# design.net
KiCad netlist of a schematic drawn in Altium Designer
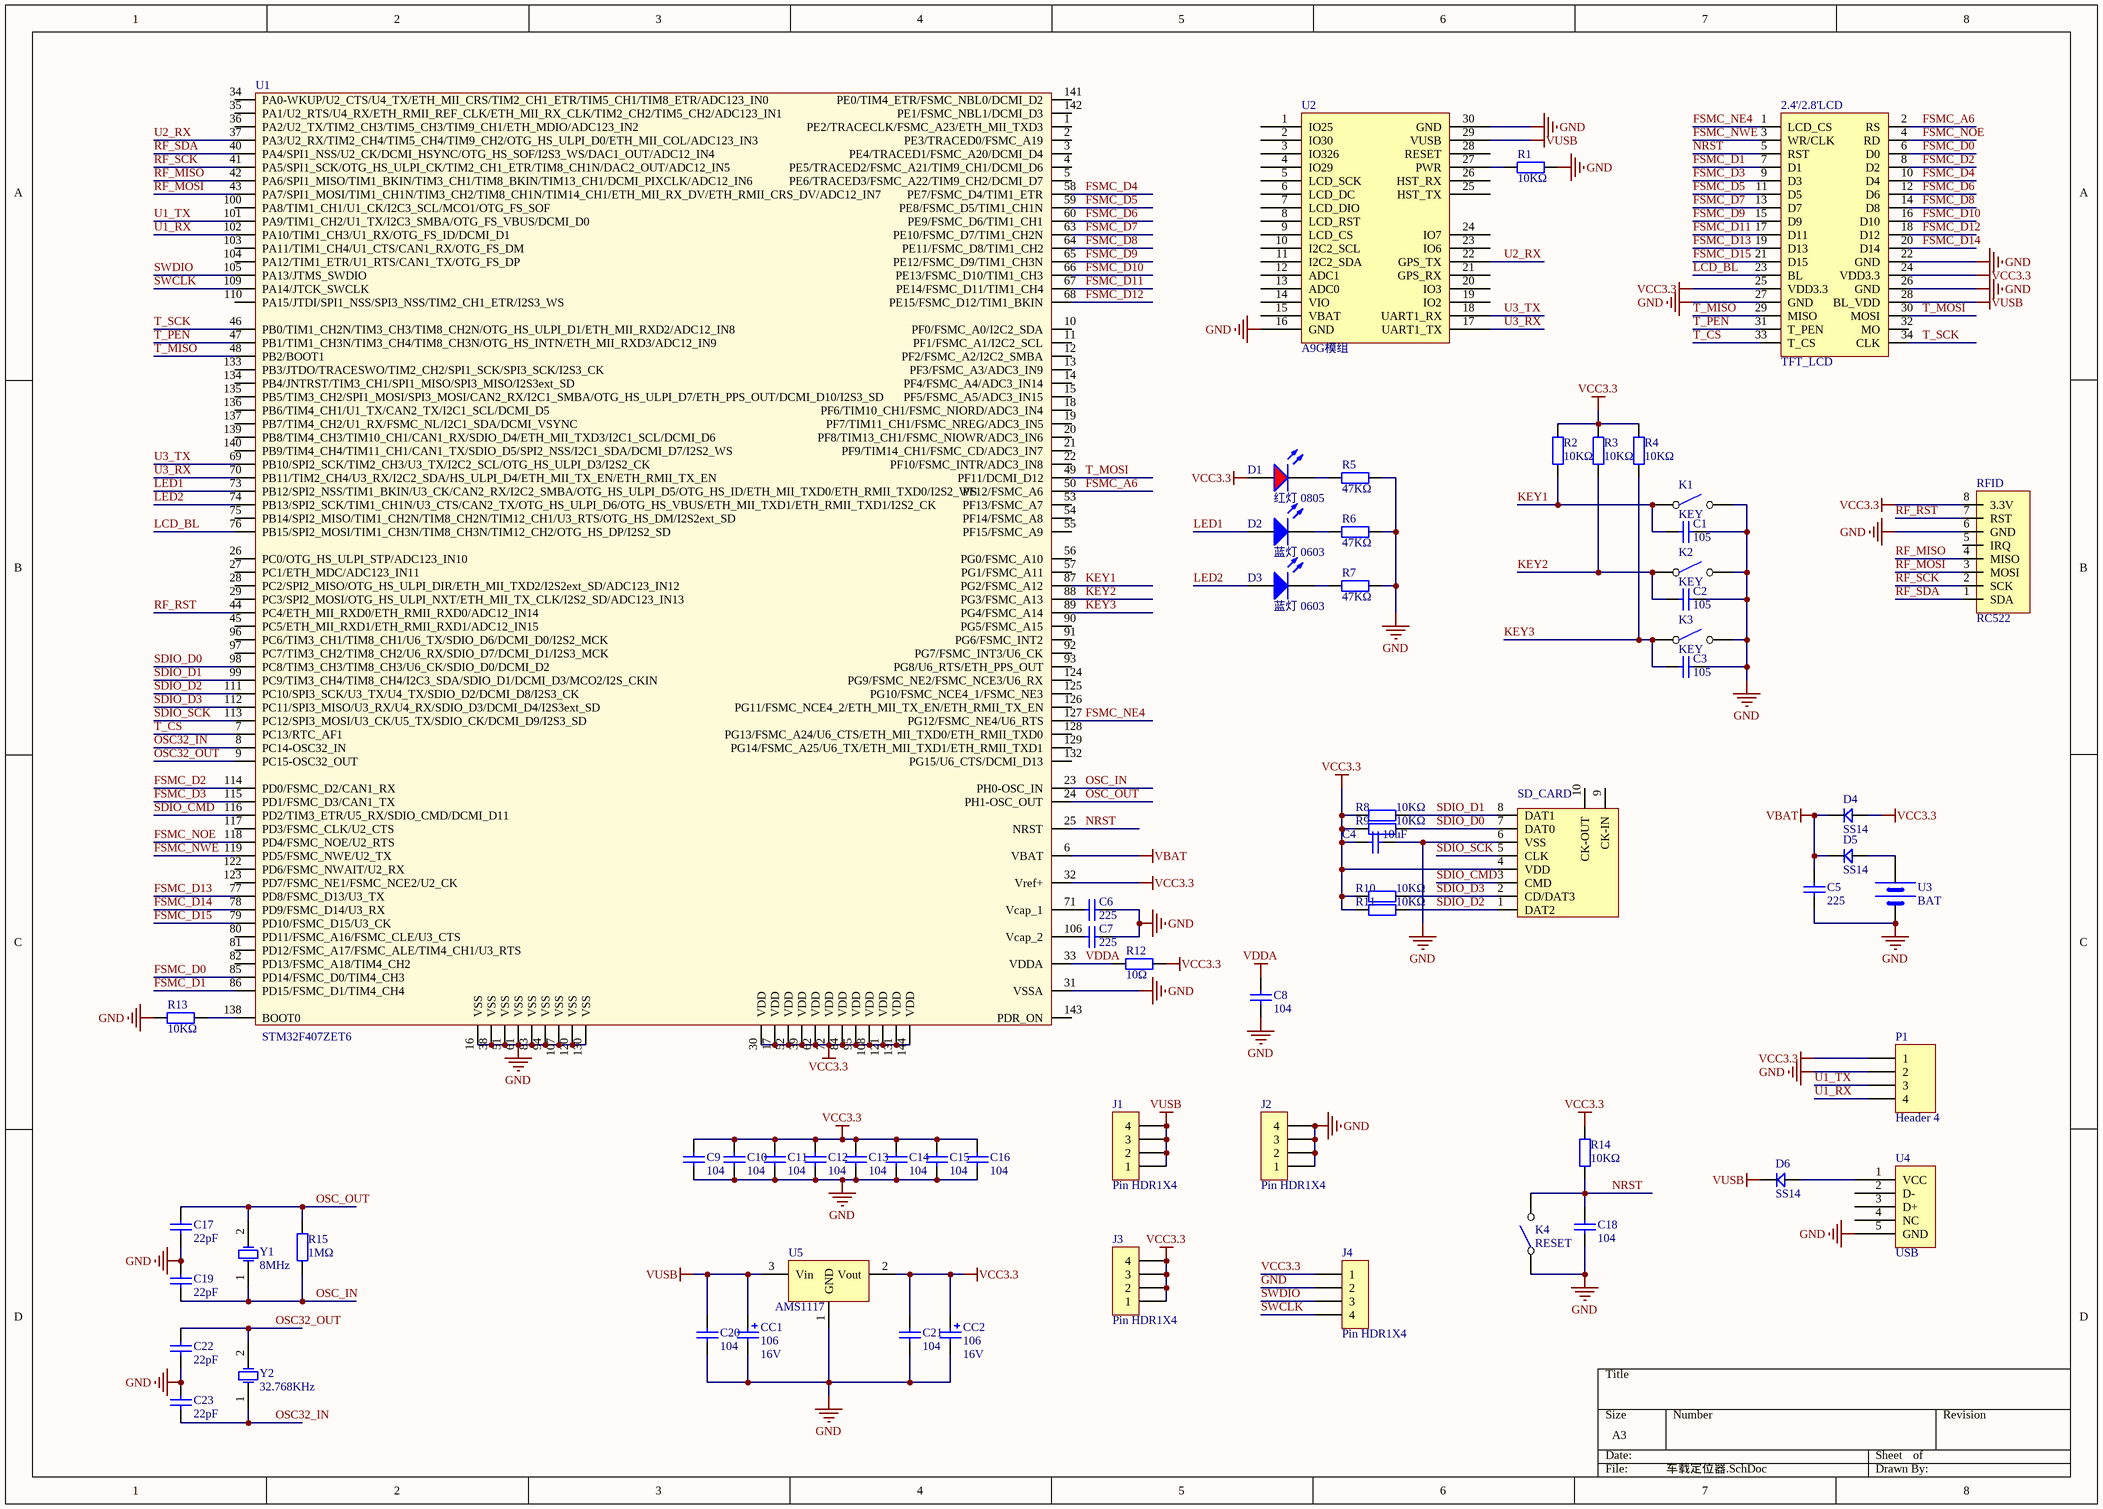
[diagram p0: 车载定位器.SchDoc]

(export (version "E")
  (design (tool "Eeschema 10.0.6"))
  (components
    (comp (ref "2.4'/2.8'LCD")
      (value "TFT_LCD")
      (footprint "TFT_LCD2.8")
      (libsource (lib "MyLib") (part "TFT_LCD"))
    )
    (comp (ref "C1")
      (value "105")
      (footprint "LC-0805_C")
      (description "贴片电容")
      (libsource (lib "Miscellaneous Devices LC") (part "0805 6.8nF (682) 10% 50V"))
    )
    (comp (ref "C2")
      (value "105")
      (footprint "LC-0805_C")
      (description "贴片电容")
      (libsource (lib "Miscellaneous Devices LC") (part "0805 6.8nF (682) 10% 50V"))
    )
    (comp (ref "C3")
      (value "105")
      (footprint "LC-0805_C")
      (description "贴片电容")
      (libsource (lib "Miscellaneous Devices LC") (part "0805 6.8nF (682) 10% 50V"))
    )
    (comp (ref "C4")
      (value "10uF")
      (footprint "LC-0805_C")
      (description "贴片电容")
      (libsource (lib "Miscellaneous Devices LC") (part "0805 10uF (106) 10% 25V"))
    )
    (comp (ref "C5")
      (value "225")
      (footprint "LC-0805_C")
      (description "贴片电容")
      (libsource (lib "Miscellaneous Devices LC") (part "0805 6.8nF (682) 10% 50V"))
    )
    (comp (ref "C6")
      (value "225")
      (footprint "LC-0805_C")
      (description "贴片电容")
      (libsource (lib "Miscellaneous Devices LC") (part "0805 6.8nF (682) 10% 50V"))
    )
    (comp (ref "C7")
      (value "225")
      (footprint "LC-0805_C")
      (description "贴片电容")
      (libsource (lib "Miscellaneous Devices LC") (part "0805 6.8nF (682) 10% 50V"))
    )
    (comp (ref "C8")
      (value "104")
      (footprint "LC-0805_C")
      (description "贴片电容")
      (libsource (lib "Miscellaneous Devices LC") (part "0805 330nF (334) 10% 50V"))
    )
    (comp (ref "C9")
      (value "104")
      (footprint "LC-0805_C")
      (description "贴片电容")
      (libsource (lib "Miscellaneous Devices LC") (part "0805 6.8nF (682) 10% 50V"))
    )
    (comp (ref "C10")
      (value "104")
      (footprint "LC-0805_C")
      (description "贴片电容")
      (libsource (lib "Miscellaneous Devices LC") (part "0805 6.8nF (682) 10% 50V"))
    )
    (comp (ref "C11")
      (value "104")
      (footprint "LC-0805_C")
      (description "贴片电容")
      (libsource (lib "Miscellaneous Devices LC") (part "0805 6.8nF (682) 10% 50V"))
    )
    (comp (ref "C12")
      (value "104")
      (footprint "LC-0805_C")
      (description "贴片电容")
      (libsource (lib "Miscellaneous Devices LC") (part "0805 6.8nF (682) 10% 50V"))
    )
    (comp (ref "C13")
      (value "104")
      (footprint "LC-0805_C")
      (description "贴片电容")
      (libsource (lib "Miscellaneous Devices LC") (part "0805 6.8nF (682) 10% 50V"))
    )
    (comp (ref "C14")
      (value "104")
      (footprint "LC-0805_C")
      (description "贴片电容")
      (libsource (lib "Miscellaneous Devices LC") (part "0805 6.8nF (682) 10% 50V"))
    )
    (comp (ref "C15")
      (value "104")
      (footprint "LC-0805_C")
      (description "贴片电容")
      (libsource (lib "Miscellaneous Devices LC") (part "0805 6.8nF (682) 10% 50V"))
    )
    (comp (ref "C16")
      (value "104")
      (footprint "LC-0805_C")
      (description "贴片电容")
      (libsource (lib "Miscellaneous Devices LC") (part "0805 6.8nF (682) 10% 50V"))
    )
    (comp (ref "C17")
      (value "22pF")
      (footprint "LC-0805_C")
      (description "贴片电容")
      (libsource (lib "Miscellaneous Devices LC") (part "0805 6pF (6R0) 0.25pF 50V"))
    )
    (comp (ref "C18")
      (value "104")
      (footprint "LC-0805_C")
      (description "贴片电容")
      (libsource (lib "Miscellaneous Devices LC") (part "0805 330nF (334) 10% 50V"))
    )
    (comp (ref "C19")
      (value "22pF")
      (footprint "LC-0805_C")
      (description "贴片电容")
      (libsource (lib "Miscellaneous Devices LC") (part "0805 6pF (6R0) 0.25pF 50V"))
    )
    (comp (ref "C20")
      (value "104")
      (footprint "LC-0805_C")
      (description "贴片电容")
      (libsource (lib "Miscellaneous Devices LC") (part "0805 6.8nF (682) 10% 50V"))
    )
    (comp (ref "C21")
      (value "104")
      (footprint "LC-0805_C")
      (description "贴片电容")
      (libsource (lib "Miscellaneous Devices LC") (part "0805 6.8nF (682) 10% 50V"))
    )
    (comp (ref "C22")
      (value "22pF")
      (footprint "LC-0805_C")
      (description "贴片电容")
      (libsource (lib "Miscellaneous Devices LC") (part "0805 6pF (6R0) 0.25pF 50V"))
    )
    (comp (ref "C23")
      (value "22pF")
      (footprint "LC-0805_C")
      (description "贴片电容")
      (libsource (lib "Miscellaneous Devices LC") (part "0805 6pF (6R0) 0.25pF 50V"))
    )
    (comp (ref "CC1")
      (value "Cap Tan C")
      (footprint "TAN-C-6032")
      (description "Polarized Capacitor (Radial)")
      (fields
        (field (name "CAPACITANCE") "106")
        (field (name "VOLTAGE") "16V")
        (field (name "PUBLISHER") "Altium Limited")
      )
      (libsource (lib "MyLib") (part "Cap Tan C"))
    )
    (comp (ref "CC2")
      (value "Cap Tan C")
      (footprint "TAN-C-6032")
      (description "Polarized Capacitor (Radial)")
      (fields
        (field (name "CAPACITANCE") "106")
        (field (name "VOLTAGE") "16V")
        (field (name "PUBLISHER") "Altium Limited")
      )
      (libsource (lib "MyLib") (part "Cap Tan C"))
    )
    (comp (ref "D1")
      (value "红灯 0805")
      (footprint "LC-0805_LED_S1")
      (description "发光二极管")
      (libsource (lib "Miscellaneous Devices LC") (part "0805 红灯"))
    )
    (comp (ref "D2")
      (value "蓝灯 0603")
      (footprint "Miscellaneous Devices LC:LC-0805_LED_S1")
      (description "发光二极管")
      (libsource (lib "Miscellaneous Devices LC") (part "0603 蓝灯"))
    )
    (comp (ref "D3")
      (value "蓝灯 0603")
      (footprint "Miscellaneous Devices LC:LC-0805_LED_S1")
      (description "发光二极管")
      (libsource (lib "Miscellaneous Devices LC") (part "0603 蓝灯"))
    )
    (comp (ref "D4")
      (value "SS14")
      (footprint "Miscellaneous Devices LC:LC-SOD-123")
      (libsource (lib "Explorer STM32F407封装库") (part "D"))
    )
    (comp (ref "D5")
      (value "SS14")
      (footprint "Miscellaneous Devices LC:LC-SOD-123")
      (libsource (lib "Explorer STM32F407封装库") (part "D"))
    )
    (comp (ref "D6")
      (value "SS14")
      (footprint "Miscellaneous Devices LC:LC-SOD-123")
      (libsource (lib "Explorer STM32F407封装库") (part "D"))
    )
    (comp (ref "J1")
      (value "Pin HDR1X4")
      (footprint "Pin HDR1X4/2.54mm-S")
      (libsource (lib "排针") (part "Pin HDR1X4"))
    )
    (comp (ref "J2")
      (value "Pin HDR1X4")
      (footprint "Pin HDR1X4/2.54mm-S")
      (libsource (lib "排针") (part "Pin HDR1X4"))
    )
    (comp (ref "J3")
      (value "Pin HDR1X4")
      (footprint "Pin HDR1X4/2.54mm-S")
      (libsource (lib "排针") (part "Pin HDR1X4"))
    )
    (comp (ref "J4")
      (value "Pin HDR1X4")
      (footprint "Pin HDR1X4/2.54mm-S")
      (libsource (lib "") (part "Pin HDR1X4_1"))
    )
    (comp (ref "K1")
      (value "KEY")
      (footprint "MyLib:KEY_2")
      (description "微动开关")
      (libsource (lib "MyLib") (part "KEY"))
    )
    (comp (ref "K2")
      (value "KEY")
      (footprint "MyLib:KEY_2")
      (description "微动开关")
      (libsource (lib "MyLib") (part "KEY"))
    )
    (comp (ref "K3")
      (value "KEY")
      (footprint "MyLib:KEY_2")
      (description "微动开关")
      (libsource (lib "MyLib") (part "KEY"))
    )
    (comp (ref "K4")
      (value "RESET")
      (footprint "MyLib:KEY_2")
      (description "微动开关")
      (libsource (lib "MyLib") (part "KEY"))
    )
    (comp (ref "P1")
      (value "Header 4")
      (footprint "MyLib:HDR1X4")
      (description "Header, 4-Pin")
      (fields (field (name "PUBLISHER") "Altium Limited"))
      (libsource (lib "MyLib") (part "Header 4"))
    )
    (comp (ref "R1")
      (value "10KΩ")
      (footprint "LC-0805_R")
      (description "贴片电阻")
      (libsource (lib "Miscellaneous Devices LC") (part "0805 10KΩ (1002) 1%"))
    )
    (comp (ref "R2")
      (value "10KΩ")
      (footprint "LC-0805_R")
      (description "贴片电阻")
      (libsource (lib "Miscellaneous Devices LC") (part "0805 11KΩ (1102) 1%"))
    )
    (comp (ref "R3")
      (value "10KΩ")
      (footprint "LC-0805_R")
      (description "贴片电阻")
      (libsource (lib "Miscellaneous Devices LC") (part "0805 11KΩ (1102) 1%"))
    )
    (comp (ref "R4")
      (value "10KΩ")
      (footprint "LC-0805_R")
      (description "贴片电阻")
      (libsource (lib "Miscellaneous Devices LC") (part "0805 11KΩ (1102) 1%"))
    )
    (comp (ref "R5")
      (value "47KΩ")
      (footprint "LC-0805_R")
      (description "贴片电阻")
      (libsource (lib "") (part "0805 11KΩ (1102) 1%_1"))
    )
    (comp (ref "R6")
      (value "47KΩ")
      (footprint "LC-0805_R")
      (description "贴片电阻")
      (libsource (lib "") (part "0805 11KΩ (1102) 1%_1"))
    )
    (comp (ref "R7")
      (value "47KΩ")
      (footprint "LC-0805_R")
      (description "贴片电阻")
      (libsource (lib "") (part "0805 11KΩ (1102) 1%_1"))
    )
    (comp (ref "R8")
      (value "10KΩ")
      (footprint "LC-0805_R")
      (description "贴片电阻")
      (libsource (lib "") (part "0805 11KΩ (1102) 1%_1"))
    )
    (comp (ref "R9")
      (value "10KΩ")
      (footprint "LC-0805_R")
      (description "贴片电阻")
      (libsource (lib "") (part "0805 11KΩ (1102) 1%_1"))
    )
    (comp (ref "R10")
      (value "10KΩ")
      (footprint "LC-0805_R")
      (description "贴片电阻")
      (libsource (lib "") (part "0805 11KΩ (1102) 1%_1"))
    )
    (comp (ref "R11")
      (value "10KΩ")
      (footprint "LC-0805_R")
      (description "贴片电阻")
      (libsource (lib "") (part "0805 11KΩ (1102) 1%_1"))
    )
    (comp (ref "R12")
      (value "10Ω")
      (footprint "LC-0805_R")
      (description "贴片电阻")
      (libsource (lib "Miscellaneous Devices LC") (part "0805 9.1KΩ (9101) 1%"))
    )
    (comp (ref "R13")
      (value "10KΩ")
      (footprint "LC-0805_R")
      (description "贴片电阻")
      (libsource (lib "Miscellaneous Devices LC") (part "0805 9.1KΩ (9101) 1%"))
    )
    (comp (ref "R14")
      (value "10KΩ")
      (footprint "LC-0805_R")
      (description "贴片电阻")
      (libsource (lib "Miscellaneous Devices LC") (part "0805 390KΩ (3903) 1%"))
    )
    (comp (ref "R15")
      (value "1MΩ")
      (footprint "LC-0805_R")
      (description "贴片电阻")
      (libsource (lib "Miscellaneous Devices LC") (part "0805 390KΩ (3903) 1%"))
    )
    (comp (ref "RFID") (value "RC522") (footprint "MyLib:RFID") (libsource (lib "MyLib") (part "RFID")))
    (comp (ref "SD_CARD")
      (value "sdIO-sdcard")
      (footprint "SD Card:Micro SD")
      (libsource (lib "战舰STM32开发板底板封装库") (part "sdIO-sdcard"))
    )
    (comp (ref "U1")
      (value "STM32F407ZET6")
      (footprint "STM32系列:LQFP144 20X20")
      (libsource (lib "Explorer STM32F407封装库") (part "STM32F407ZET6"))
    )
    (comp (ref "U2") (value "A9G模组") (footprint "车载定位器:A9G") (libsource (lib "车载定位器") (part "A9G模组")))
    (comp (ref "U3")
      (value "BAT")
      (footprint "MyLib:CR1220_A")
      (description "纽扣电池座CR1220")
      (libsource (lib "MyLib") (part "BAT"))
    )
    (comp (ref "U4") (value "USB") (footprint "MyLib:USB_B") (libsource (lib "MyLib") (part "USB")))
    (comp (ref "U5")
      (value "AMS1117")
      (footprint "MyLib:SOT-223")
      (description "3.3V电压转换器AMS1117")
      (libsource (lib "My Footprint") (part "AMS1117"))
    )
    (comp (ref "Y1")
      (value "8MHz")
      (footprint "MyLib:XTAL-SMD")
      (description "晶体振荡器")
      (fields (field (name "PUBLISHER") "Altium Limited"))
      (libsource (lib "MyLib") (part "XTAL"))
    )
    (comp (ref "Y2")
      (value "32.768KHz")
      (footprint "晶振:OSC-3x8-WI-B")
      (description "晶体振荡器")
      (fields (field (name "PUBLISHER") "Altium Limited"))
      (libsource (lib "MyLib") (part "XTAL"))
    )
  )
  (nets
    (net (code "1") (name "/FSMC_A6") (class "Default")
      (node (ref "2.4'/2.8'LCD") (pin "2") (pinfunction "RS_2") (pintype "passive"))
      (node (ref "U1") (pin "50") (pinfunction "PF12/FSMC_A6_50") (pintype "passive"))
    )
    (net (code "2") (name "/FSMC_D0") (class "Default")
      (node (ref "2.4'/2.8'LCD") (pin "6") (pinfunction "D0_6") (pintype "passive"))
      (node (ref "U1") (pin "85") (pinfunction "PD14/FSMC_D0/TIM4_CH3_85") (pintype "passive"))
    )
    (net (code "3") (name "/FSMC_D1") (class "Default")
      (node (ref "2.4'/2.8'LCD") (pin "7") (pinfunction "D1_7") (pintype "passive"))
      (node (ref "U1") (pin "86") (pinfunction "PD15/FSMC_D1/TIM4_CH4_86") (pintype "passive"))
    )
    (net (code "4") (name "/FSMC_D2") (class "Default")
      (node (ref "2.4'/2.8'LCD") (pin "8") (pinfunction "D2_8") (pintype "passive"))
      (node (ref "U1") (pin "114") (pinfunction "PD0/FSMC_D2/CAN1_RX_114") (pintype "passive"))
    )
    (net (code "5") (name "/FSMC_D3") (class "Default")
      (node (ref "2.4'/2.8'LCD") (pin "9") (pinfunction "D3_9") (pintype "passive"))
      (node (ref "U1") (pin "115") (pinfunction "PD1/FSMC_D3/CAN1_TX_115") (pintype "passive"))
    )
    (net (code "6") (name "/FSMC_D4") (class "Default")
      (node (ref "2.4'/2.8'LCD") (pin "10") (pinfunction "D4_10") (pintype "passive"))
      (node (ref "U1") (pin "58") (pinfunction "PE7/FSMC_D4/TIM1_ETR_58") (pintype "passive"))
    )
    (net (code "7") (name "/FSMC_D5") (class "Default")
      (node (ref "2.4'/2.8'LCD") (pin "11") (pinfunction "D5_11") (pintype "passive"))
      (node (ref "U1") (pin "59") (pinfunction "PE8/FSMC_D5/TIM1_CH1N_59") (pintype "passive"))
    )
    (net (code "8") (name "/FSMC_D6") (class "Default")
      (node (ref "2.4'/2.8'LCD") (pin "12") (pinfunction "D6_12") (pintype "passive"))
      (node (ref "U1") (pin "60") (pinfunction "PE9/FSMC_D6/TIM1_CH1_60") (pintype "passive"))
    )
    (net (code "9") (name "/FSMC_D7") (class "Default")
      (node (ref "2.4'/2.8'LCD") (pin "13") (pinfunction "D7_13") (pintype "passive"))
      (node (ref "U1") (pin "63") (pinfunction "PE10/FSMC_D7/TIM1_CH2N_63") (pintype "passive"))
    )
    (net (code "10") (name "/FSMC_D8") (class "Default")
      (node (ref "2.4'/2.8'LCD") (pin "14") (pinfunction "D8_14") (pintype "passive"))
      (node (ref "U1") (pin "64") (pinfunction "PE11/FSMC_D8/TIM1_CH2_64") (pintype "passive"))
    )
    (net (code "11") (name "/FSMC_D9") (class "Default")
      (node (ref "2.4'/2.8'LCD") (pin "15") (pinfunction "D9_15") (pintype "passive"))
      (node (ref "U1") (pin "65") (pinfunction "PE12/FSMC_D9/TIM1_CH3N_65") (pintype "passive"))
    )
    (net (code "12") (name "/FSMC_D10") (class "Default")
      (node (ref "2.4'/2.8'LCD") (pin "16") (pinfunction "D10_16") (pintype "passive"))
      (node (ref "U1") (pin "66") (pinfunction "PE13/FSMC_D10/TIM1_CH3_66") (pintype "passive"))
    )
    (net (code "13") (name "/FSMC_D11") (class "Default")
      (node (ref "2.4'/2.8'LCD") (pin "17") (pinfunction "D11_17") (pintype "passive"))
      (node (ref "U1") (pin "67") (pinfunction "PE14/FSMC_D11/TIM1_CH4_67") (pintype "passive"))
    )
    (net (code "14") (name "/FSMC_D12") (class "Default")
      (node (ref "2.4'/2.8'LCD") (pin "18") (pinfunction "D12_18") (pintype "passive"))
      (node (ref "U1") (pin "68") (pinfunction "PE15/FSMC_D12/TIM1_BKIN_68") (pintype "passive"))
    )
    (net (code "15") (name "/FSMC_D13") (class "Default")
      (node (ref "2.4'/2.8'LCD") (pin "19") (pinfunction "D13_19") (pintype "passive"))
      (node (ref "U1") (pin "77") (pinfunction "PD8/FSMC_D13/U3_TX_77") (pintype "passive"))
    )
    (net (code "16") (name "/FSMC_D14") (class "Default")
      (node (ref "2.4'/2.8'LCD") (pin "20") (pinfunction "D14_20") (pintype "passive"))
      (node (ref "U1") (pin "78") (pinfunction "PD9/FSMC_D14/U3_RX_78") (pintype "passive"))
    )
    (net (code "17") (name "/FSMC_D15") (class "Default")
      (node (ref "2.4'/2.8'LCD") (pin "21") (pinfunction "D15_21") (pintype "passive"))
      (node (ref "U1") (pin "79") (pinfunction "PD10/FSMC_D15/U3_CK_79") (pintype "passive"))
    )
    (net (code "18") (name "/FSMC_NE4") (class "Default")
      (node (ref "2.4'/2.8'LCD") (pin "1") (pinfunction "LCD_CS_1") (pintype "passive"))
      (node (ref "U1") (pin "127") (pinfunction "PG12/FSMC_NE4/U6_RTS_127") (pintype "passive"))
    )
    (net (code "19") (name "/FSMC_NOE") (class "Default")
      (node (ref "2.4'/2.8'LCD") (pin "4") (pinfunction "RD_4") (pintype "passive"))
      (node (ref "U1") (pin "118") (pinfunction "PD4/FSMC_NOE/U2_RTS_118") (pintype "passive"))
    )
    (net (code "20") (name "/FSMC_NWE") (class "Default")
      (node (ref "2.4'/2.8'LCD") (pin "3") (pinfunction "WR/CLK_3") (pintype "passive"))
      (node (ref "U1") (pin "119") (pinfunction "PD5/FSMC_NWE/U2_TX_119") (pintype "passive"))
    )
    (net (code "21") (name "/KEY1") (class "Default")
      (node (ref "C1") (pin "1") (pinfunction "1_1") (pintype "passive"))
      (node (ref "K1") (pin "1") (pinfunction "1_1") (pintype "passive"))
      (node (ref "R2") (pin "1") (pinfunction "1_1") (pintype "passive"))
      (node (ref "U1") (pin "87") (pinfunction "PG2/FSMC_A12_87") (pintype "passive"))
    )
    (net (code "22") (name "/KEY2") (class "Default")
      (node (ref "C2") (pin "1") (pinfunction "1_1") (pintype "passive"))
      (node (ref "K2") (pin "1") (pinfunction "1_1") (pintype "passive"))
      (node (ref "R3") (pin "1") (pinfunction "1_1") (pintype "passive"))
      (node (ref "U1") (pin "88") (pinfunction "PG3/FSMC_A13_88") (pintype "passive"))
    )
    (net (code "23") (name "/KEY3") (class "Default")
      (node (ref "C3") (pin "1") (pinfunction "1_1") (pintype "passive"))
      (node (ref "K3") (pin "1") (pinfunction "1_1") (pintype "passive"))
      (node (ref "R4") (pin "1") (pinfunction "1_1") (pintype "passive"))
      (node (ref "U1") (pin "89") (pinfunction "PG4/FSMC_A14_89") (pintype "passive"))
    )
    (net (code "24") (name "/LCD_BL") (class "Default")
      (node (ref "2.4'/2.8'LCD") (pin "23") (pinfunction "BL_23") (pintype "passive"))
      (node (ref "U1") (pin "76") (pinfunction "PB15/SPI2_MOSI/TIM1_CH3N/TIM8_CH3N/TIM12_CH2/OTG_HS_DP/I2S2_SD_76") (pintype "passive"))
    )
    (net (code "25") (name "/LED1") (class "Default")
      (node (ref "D2") (pin "A") (pinfunction "A_A") (pintype "passive"))
      (node (ref "U1") (pin "73") (pinfunction "PB12/SPI2_NSS/TIM1_BKIN/U3_CK/CAN2_RX/I2C2_SMBA/OTG_HS_ULPI_D5/OTG_HS_ID/ETH_MII_TXD0/ETH_RMII_TXD0/I2S2_WS_73") (pintype "passive"))
    )
    (net (code "26") (name "/LED2") (class "Default")
      (node (ref "D3") (pin "A") (pinfunction "A_A") (pintype "passive"))
      (node (ref "U1") (pin "74") (pinfunction "PB13/SPI2_SCK/TIM1_CH1N/U3_CTS/CAN2_TX/OTG_HS_ULPI_D6/OTG_HS_VBUS/ETH_MII_TXD1/ETH_RMII_TXD1/I2S2_CK_74") (pintype "passive"))
    )
    (net (code "27") (name "/NRST") (class "Default")
      (node (ref "2.4'/2.8'LCD") (pin "5") (pinfunction "RST_5") (pintype "passive"))
      (node (ref "C18") (pin "2") (pinfunction "2_2") (pintype "passive"))
      (node (ref "K4") (pin "2") (pinfunction "2_2") (pintype "passive"))
      (node (ref "R14") (pin "1") (pinfunction "1_1") (pintype "passive"))
      (node (ref "U1") (pin "25") (pinfunction "NRST_25") (pintype "passive"))
    )
    (net (code "28") (name "/OSC32_IN") (class "Default")
      (node (ref "C23") (pin "1") (pinfunction "1_1") (pintype "passive"))
      (node (ref "U1") (pin "8") (pinfunction "PC14-OSC32_IN_8") (pintype "passive"))
      (node (ref "Y2") (pin "1") (pinfunction "OSC1_1") (pintype "passive"))
    )
    (net (code "29") (name "/OSC32_OUT") (class "Default")
      (node (ref "C22") (pin "2") (pinfunction "2_2") (pintype "passive"))
      (node (ref "U1") (pin "9") (pinfunction "PC15-OSC32_OUT_9") (pintype "passive"))
      (node (ref "Y2") (pin "2") (pinfunction "OSC2_2") (pintype "passive"))
    )
    (net (code "30") (name "/OSC_IN") (class "Default")
      (node (ref "C19") (pin "1") (pinfunction "1_1") (pintype "passive"))
      (node (ref "R15") (pin "1") (pinfunction "1_1") (pintype "passive"))
      (node (ref "U1") (pin "23") (pinfunction "PH0-OSC_IN_23") (pintype "passive"))
      (node (ref "Y1") (pin "1") (pinfunction "OSC1_1") (pintype "passive"))
    )
    (net (code "31") (name "/OSC_OUT") (class "Default")
      (node (ref "C17") (pin "2") (pinfunction "2_2") (pintype "passive"))
      (node (ref "R15") (pin "2") (pinfunction "2_2") (pintype "passive"))
      (node (ref "U1") (pin "24") (pinfunction "PH1-OSC_OUT_24") (pintype "passive"))
      (node (ref "Y1") (pin "2") (pinfunction "OSC2_2") (pintype "passive"))
    )
    (net (code "32") (name "/RF_MISO") (class "Default")
      (node (ref "RFID") (pin "4") (pinfunction "MISO_4") (pintype "passive"))
      (node (ref "U1") (pin "42") (pinfunction "PA6/SPI1_MISO/TIM1_BKIN/TIM3_CH1/TIM8_BKIN/TIM13_CH1/DCMI_PIXCLK/ADC12_IN6_42") (pintype "passive"))
    )
    (net (code "33") (name "/RF_MOSI") (class "Default")
      (node (ref "RFID") (pin "3") (pinfunction "MOSI_3") (pintype "passive"))
      (node (ref "U1") (pin "43") (pinfunction "PA7/SPI1_MOSI/TIM1_CH1N/TIM3_CH2/TIM8_CH1N/TIM14_CH1/ETH_MII_RX_DV/ETH_RMII_CRS_DV/ADC12_IN7_43") (pintype "passive"))
    )
    (net (code "34") (name "/RF_RST") (class "Default")
      (node (ref "RFID") (pin "7") (pinfunction "RST_7") (pintype "passive"))
      (node (ref "U1") (pin "44") (pinfunction "PC4/ETH_MII_RXD0/ETH_RMII_RXD0/ADC12_IN14_44") (pintype "passive"))
    )
    (net (code "35") (name "/RF_SCK") (class "Default")
      (node (ref "RFID") (pin "2") (pinfunction "SCK_2") (pintype "passive"))
      (node (ref "U1") (pin "41") (pinfunction "PA5/SPI1_SCK/OTG_HS_ULPI_CK/TIM2_CH1_ETR/TIM8_CH1N/DAC2_OUT/ADC12_IN5_41") (pintype "passive"))
    )
    (net (code "36") (name "/RF_SDA") (class "Default")
      (node (ref "RFID") (pin "1") (pinfunction "SDA_1") (pintype "passive"))
      (node (ref "U1") (pin "40") (pinfunction "PA4/SPI1_NSS/U2_CK/DCMI_HSYNC/OTG_HS_SOF/I2S3_WS/DAC1_OUT/ADC12_IN4_40") (pintype "passive"))
    )
    (net (code "37") (name "/SDIO_CMD") (class "Default")
      (node (ref "SD_CARD") (pin "3") (pinfunction "CMD_3") (pintype "passive"))
      (node (ref "U1") (pin "116") (pinfunction "PD2/TIM3_ETR/U5_RX/SDIO_CMD/DCMI_D11_116") (pintype "passive"))
    )
    (net (code "38") (name "/SDIO_D0") (class "Default")
      (node (ref "R9") (pin "2") (pinfunction "2_2") (pintype "passive"))
      (node (ref "SD_CARD") (pin "7") (pinfunction "DAT0_7") (pintype "passive"))
      (node (ref "U1") (pin "98") (pinfunction "PC8/TIM3_CH3/TIM8_CH3/U6_CK/SDIO_D0/DCMI_D2_98") (pintype "passive"))
    )
    (net (code "39") (name "/SDIO_D1") (class "Default")
      (node (ref "R8") (pin "2") (pinfunction "2_2") (pintype "passive"))
      (node (ref "SD_CARD") (pin "8") (pinfunction "DAT1_8") (pintype "passive"))
      (node (ref "U1") (pin "99") (pinfunction "PC9/TIM3_CH4/TIM8_CH4/I2C3_SDA/SDIO_D1/DCMI_D3/MCO2/I2S_CKIN_99") (pintype "passive"))
    )
    (net (code "40") (name "/SDIO_D2") (class "Default")
      (node (ref "R11") (pin "2") (pinfunction "2_2") (pintype "passive"))
      (node (ref "SD_CARD") (pin "1") (pinfunction "DAT2_1") (pintype "passive"))
      (node (ref "U1") (pin "111") (pinfunction "PC10/SPI3_SCK/U3_TX/U4_TX/SDIO_D2/DCMI_D8/I2S3_CK_111") (pintype "passive"))
    )
    (net (code "41") (name "/SDIO_D3") (class "Default")
      (node (ref "R10") (pin "2") (pinfunction "2_2") (pintype "passive"))
      (node (ref "SD_CARD") (pin "2") (pinfunction "CD/DAT3_2") (pintype "passive"))
      (node (ref "U1") (pin "112") (pinfunction "PC11/SPI3_MISO/U3_RX/U4_RX/SDIO_D3/DCMI_D4/I2S3ext_SD_112") (pintype "passive"))
    )
    (net (code "42") (name "/SDIO_SCK") (class "Default")
      (node (ref "SD_CARD") (pin "5") (pinfunction "CLK_5") (pintype "passive"))
      (node (ref "U1") (pin "113") (pinfunction "PC12/SPI3_MOSI/U3_CK/U5_TX/SDIO_CK/DCMI_D9/I2S3_SD_113") (pintype "passive"))
    )
    (net (code "43") (name "/SWCLK") (class "Default")
      (node (ref "J4") (pin "4") (pinfunction "4_4") (pintype "passive"))
      (node (ref "U1") (pin "109") (pinfunction "PA14/JTCK_SWCLK_109") (pintype "passive"))
    )
    (net (code "44") (name "/SWDIO") (class "Default")
      (node (ref "J4") (pin "3") (pinfunction "3_3") (pintype "passive"))
      (node (ref "U1") (pin "105") (pinfunction "PA13/JTMS_SWDIO_105") (pintype "passive"))
    )
    (net (code "45") (name "/T_CS") (class "Default")
      (node (ref "2.4'/2.8'LCD") (pin "33") (pinfunction "T_CS_33") (pintype "passive"))
      (node (ref "U1") (pin "7") (pinfunction "PC13/RTC_AF1_7") (pintype "passive"))
    )
    (net (code "46") (name "/T_MISO") (class "Default")
      (node (ref "2.4'/2.8'LCD") (pin "29") (pinfunction "MISO_29") (pintype "passive"))
      (node (ref "U1") (pin "48") (pinfunction "PB2/BOOT1_48") (pintype "passive"))
    )
    (net (code "47") (name "/T_MOSI") (class "Default")
      (node (ref "2.4'/2.8'LCD") (pin "30") (pinfunction "MOSI_30") (pintype "passive"))
      (node (ref "U1") (pin "49") (pinfunction "PF11/DCMI_D12_49") (pintype "passive"))
    )
    (net (code "48") (name "/T_PEN") (class "Default")
      (node (ref "2.4'/2.8'LCD") (pin "31") (pinfunction "T_PEN_31") (pintype "passive"))
      (node (ref "U1") (pin "47") (pinfunction "PB1/TIM1_CH3N/TIM3_CH4/TIM8_CH3N/OTG_HS_INTN/ETH_MII_RXD3/ADC12_IN9_47") (pintype "passive"))
    )
    (net (code "49") (name "/T_SCK") (class "Default")
      (node (ref "2.4'/2.8'LCD") (pin "34") (pinfunction "CLK_34") (pintype "passive"))
      (node (ref "U1") (pin "46") (pinfunction "PB0/TIM1_CH2N/TIM3_CH3/TIM8_CH2N/OTG_HS_ULPI_D1/ETH_MII_RXD2/ADC12_IN8_46") (pintype "passive"))
    )
    (net (code "50") (name "/U1_RX") (class "Default")
      (node (ref "P1") (pin "4") (pinfunction "4_4") (pintype "passive"))
      (node (ref "U1") (pin "102") (pinfunction "PA10/TIM1_CH3/U1_RX/OTG_FS_ID/DCMI_D1_102") (pintype "passive"))
    )
    (net (code "51") (name "/U1_TX") (class "Default")
      (node (ref "P1") (pin "3") (pinfunction "3_3") (pintype "passive"))
      (node (ref "U1") (pin "101") (pinfunction "PA9/TIM1_CH2/U1_TX/I2C3_SMBA/OTG_FS_VBUS/DCMI_D0_101") (pintype "passive"))
    )
    (net (code "52") (name "/U2_RX") (class "Default")
      (node (ref "U1") (pin "37") (pinfunction "PA3/U2_RX/TIM2_CH4/TIM5_CH4/TIM9_CH2/OTG_HS_ULPI_D0/ETH_MII_COL/ADC123_IN3_37") (pintype "passive"))
      (node (ref "U2") (pin "22") (pinfunction "GPS_TX_22") (pintype "passive"))
    )
    (net (code "53") (name "/U3_RX") (class "Default")
      (node (ref "U1") (pin "70") (pinfunction "PB11/TIM2_CH4/U3_RX/I2C2_SDA/HS_ULPI_D4/ETH_MII_TX_EN/ETH_RMII_TX_EN_70") (pintype "passive"))
      (node (ref "U2") (pin "17") (pinfunction "UART1_TX_17") (pintype "passive"))
    )
    (net (code "54") (name "/U3_TX") (class "Default")
      (node (ref "U1") (pin "69") (pinfunction "PB10/SPI2_SCK/TIM2_CH3/U3_TX/I2C2_SCL/OTG_HS_ULPI_D3/I2S2_CK_69") (pintype "passive"))
      (node (ref "U2") (pin "18") (pinfunction "UART1_RX_18") (pintype "passive"))
    )
    (net (code "55") (name "GND") (class "Default")
      (node (ref "2.4'/2.8'LCD") (pin "22") (pinfunction "GND_22") (pintype "passive"))
      (node (ref "2.4'/2.8'LCD") (pin "26") (pinfunction "GND_26") (pintype "passive"))
      (node (ref "2.4'/2.8'LCD") (pin "27") (pinfunction "GND_27") (pintype "passive"))
      (node (ref "C1") (pin "2") (pinfunction "2_2") (pintype "passive"))
      (node (ref "C10") (pin "1") (pinfunction "1_1") (pintype "passive"))
      (node (ref "C11") (pin "1") (pinfunction "1_1") (pintype "passive"))
      (node (ref "C12") (pin "1") (pinfunction "1_1") (pintype "passive"))
      (node (ref "C13") (pin "1") (pinfunction "1_1") (pintype "passive"))
      (node (ref "C14") (pin "1") (pinfunction "1_1") (pintype "passive"))
      (node (ref "C15") (pin "1") (pinfunction "1_1") (pintype "passive"))
      (node (ref "C16") (pin "1") (pinfunction "1_1") (pintype "passive"))
      (node (ref "C17") (pin "1") (pinfunction "1_1") (pintype "passive"))
      (node (ref "C18") (pin "1") (pinfunction "1_1") (pintype "passive"))
      (node (ref "C19") (pin "2") (pinfunction "2_2") (pintype "passive"))
      (node (ref "C2") (pin "2") (pinfunction "2_2") (pintype "passive"))
      (node (ref "C20") (pin "1") (pinfunction "1_1") (pintype "passive"))
      (node (ref "C21") (pin "1") (pinfunction "1_1") (pintype "passive"))
      (node (ref "C22") (pin "1") (pinfunction "1_1") (pintype "passive"))
      (node (ref "C23") (pin "2") (pinfunction "2_2") (pintype "passive"))
      (node (ref "C3") (pin "2") (pinfunction "2_2") (pintype "passive"))
      (node (ref "C4") (pin "2") (pinfunction "2_2") (pintype "passive"))
      (node (ref "C5") (pin "1") (pinfunction "1_1") (pintype "passive"))
      (node (ref "C6") (pin "2") (pinfunction "2_2") (pintype "passive"))
      (node (ref "C7") (pin "2") (pinfunction "2_2") (pintype "passive"))
      (node (ref "C8") (pin "1") (pinfunction "1_1") (pintype "passive"))
      (node (ref "C9") (pin "1") (pinfunction "1_1") (pintype "passive"))
      (node (ref "CC1") (pin "1") (pinfunction "2_1") (pintype "passive"))
      (node (ref "CC2") (pin "1") (pinfunction "2_1") (pintype "passive"))
      (node (ref "J2") (pin "1") (pinfunction "1_1") (pintype "passive"))
      (node (ref "J2") (pin "2") (pinfunction "2_2") (pintype "passive"))
      (node (ref "J2") (pin "3") (pinfunction "3_3") (pintype "passive"))
      (node (ref "J2") (pin "4") (pinfunction "4_4") (pintype "passive"))
      (node (ref "J4") (pin "2") (pinfunction "2_2") (pintype "passive"))
      (node (ref "K1") (pin "2") (pinfunction "2_2") (pintype "passive"))
      (node (ref "K2") (pin "2") (pinfunction "2_2") (pintype "passive"))
      (node (ref "K3") (pin "2") (pinfunction "2_2") (pintype "passive"))
      (node (ref "K4") (pin "1") (pinfunction "1_1") (pintype "passive"))
      (node (ref "P1") (pin "2") (pinfunction "2_2") (pintype "passive"))
      (node (ref "R1") (pin "2") (pinfunction "2_2") (pintype "passive"))
      (node (ref "R13") (pin "1") (pinfunction "1_1") (pintype "passive"))
      (node (ref "R5") (pin "2") (pinfunction "2_2") (pintype "passive"))
      (node (ref "R6") (pin "2") (pinfunction "2_2") (pintype "passive"))
      (node (ref "R7") (pin "2") (pinfunction "2_2") (pintype "passive"))
      (node (ref "RFID") (pin "6") (pinfunction "GND_6") (pintype "passive"))
      (node (ref "SD_CARD") (pin "6") (pinfunction "VSS_6") (pintype "passive"))
      (node (ref "U1") (pin "107") (pinfunction "VSS_107") (pintype "passive"))
      (node (ref "U1") (pin "120") (pinfunction "VSS_120") (pintype "passive"))
      (node (ref "U1") (pin "130") (pinfunction "VSS_130") (pintype "passive"))
      (node (ref "U1") (pin "16") (pinfunction "VSS_16") (pintype "passive"))
      (node (ref "U1") (pin "31") (pinfunction "VSSA_31") (pintype "passive"))
      (node (ref "U1") (pin "38") (pinfunction "VSS_38") (pintype "passive"))
      (node (ref "U1") (pin "51") (pinfunction "VSS_51") (pintype "passive"))
      (node (ref "U1") (pin "61") (pinfunction "VSS_61") (pintype "passive"))
      (node (ref "U1") (pin "83") (pinfunction "VSS_83") (pintype "passive"))
      (node (ref "U1") (pin "94") (pinfunction "VSS_94") (pintype "passive"))
      (node (ref "U2") (pin "16") (pinfunction "GND_16") (pintype "passive"))
      (node (ref "U2") (pin "30") (pinfunction "GND_30") (pintype "passive"))
      (node (ref "U3") (pin "2") (pinfunction "GND_2") (pintype "passive"))
      (node (ref "U4") (pin "5") (pinfunction "GND_5") (pintype "passive"))
      (node (ref "U5") (pin "1") (pinfunction "GND_1") (pintype "passive"))
    )
    (net (code "56") (name "Net-(D1-PadK)") (class "Default")
      (node (ref "D1") (pin "K") (pinfunction "K_K") (pintype "passive"))
      (node (ref "R5") (pin "1") (pinfunction "1_1") (pintype "passive"))
    )
    (net (code "57") (name "Net-(D2-PadK)") (class "Default")
      (node (ref "D2") (pin "K") (pinfunction "K_K") (pintype "passive"))
      (node (ref "R6") (pin "1") (pinfunction "1_1") (pintype "passive"))
    )
    (net (code "58") (name "Net-(D3-PadK)") (class "Default")
      (node (ref "D3") (pin "K") (pinfunction "K_K") (pintype "passive"))
      (node (ref "R7") (pin "1") (pinfunction "1_1") (pintype "passive"))
    )
    (net (code "59") (name "Net-(U1-BOOT0)") (class "Default")
      (node (ref "R13") (pin "2") (pinfunction "2_2") (pintype "passive"))
      (node (ref "U1") (pin "138") (pinfunction "BOOT0_138") (pintype "passive"))
    )
    (net (code "60") (name "Net-(U1-Vcap_1)") (class "Default")
      (node (ref "C6") (pin "1") (pinfunction "1_1") (pintype "passive"))
      (node (ref "U1") (pin "71") (pinfunction "Vcap_1_71") (pintype "passive"))
    )
    (net (code "61") (name "Net-(U1-Vcap_2)") (class "Default")
      (node (ref "C7") (pin "1") (pinfunction "1_1") (pintype "passive"))
      (node (ref "U1") (pin "106") (pinfunction "Vcap_2_106") (pintype "passive"))
    )
    (net (code "62") (name "Net-(U2-PWR)") (class "Default")
      (node (ref "R1") (pin "1") (pinfunction "1_1") (pintype "passive"))
      (node (ref "U2") (pin "27") (pinfunction "PWR_27") (pintype "passive"))
    )
    (net (code "63") (name "Net-(U3-VCC)") (class "Default")
      (node (ref "D5") (pin "1") (pintype "passive"))
      (node (ref "U3") (pin "1") (pinfunction "VCC_1") (pintype "passive"))
    )
    (net (code "64") (name "Net-(U4-VCC)") (class "Default")
      (node (ref "D6") (pin "1") (pintype "passive"))
      (node (ref "U4") (pin "1") (pinfunction "VCC_1") (pintype "passive"))
    )
    (net (code "65") (name "VBAT") (class "Default")
      (node (ref "C5") (pin "2") (pinfunction "2_2") (pintype "passive"))
      (node (ref "D4") (pin "2") (pintype "passive"))
      (node (ref "D5") (pin "2") (pintype "passive"))
      (node (ref "U1") (pin "6") (pinfunction "VBAT_6") (pintype "passive"))
    )
    (net (code "66") (name "VCC3.3") (class "Default")
      (node (ref "2.4'/2.8'LCD") (pin "24") (pinfunction "VDD3.3_24") (pintype "passive"))
      (node (ref "2.4'/2.8'LCD") (pin "25") (pinfunction "VDD3.3_25") (pintype "passive"))
      (node (ref "C10") (pin "2") (pinfunction "2_2") (pintype "passive"))
      (node (ref "C11") (pin "2") (pinfunction "2_2") (pintype "passive"))
      (node (ref "C12") (pin "2") (pinfunction "2_2") (pintype "passive"))
      (node (ref "C13") (pin "2") (pinfunction "2_2") (pintype "passive"))
      (node (ref "C14") (pin "2") (pinfunction "2_2") (pintype "passive"))
      (node (ref "C15") (pin "2") (pinfunction "2_2") (pintype "passive"))
      (node (ref "C16") (pin "2") (pinfunction "2_2") (pintype "passive"))
      (node (ref "C21") (pin "2") (pinfunction "2_2") (pintype "passive"))
      (node (ref "C4") (pin "1") (pinfunction "1_1") (pintype "passive"))
      (node (ref "C9") (pin "2") (pinfunction "2_2") (pintype "passive"))
      (node (ref "CC2") (pin "2") (pinfunction "1_2") (pintype "passive"))
      (node (ref "D1") (pin "A") (pinfunction "A_A") (pintype "passive"))
      (node (ref "D4") (pin "1") (pintype "passive"))
      (node (ref "J3") (pin "1") (pinfunction "1_1") (pintype "passive"))
      (node (ref "J3") (pin "2") (pinfunction "2_2") (pintype "passive"))
      (node (ref "J3") (pin "3") (pinfunction "3_3") (pintype "passive"))
      (node (ref "J3") (pin "4") (pinfunction "4_4") (pintype "passive"))
      (node (ref "J4") (pin "1") (pinfunction "1_1") (pintype "passive"))
      (node (ref "P1") (pin "1") (pinfunction "1_1") (pintype "passive"))
      (node (ref "R10") (pin "1") (pinfunction "1_1") (pintype "passive"))
      (node (ref "R11") (pin "1") (pinfunction "1_1") (pintype "passive"))
      (node (ref "R12") (pin "2") (pinfunction "2_2") (pintype "passive"))
      (node (ref "R14") (pin "2") (pinfunction "2_2") (pintype "passive"))
      (node (ref "R2") (pin "2") (pinfunction "2_2") (pintype "passive"))
      (node (ref "R3") (pin "2") (pinfunction "2_2") (pintype "passive"))
      (node (ref "R4") (pin "2") (pinfunction "2_2") (pintype "passive"))
      (node (ref "R8") (pin "1") (pinfunction "1_1") (pintype "passive"))
      (node (ref "R9") (pin "1") (pinfunction "1_1") (pintype "passive"))
      (node (ref "RFID") (pin "8") (pinfunction "3.3V_8") (pintype "passive"))
      (node (ref "SD_CARD") (pin "4") (pinfunction "VDD_4") (pintype "passive"))
      (node (ref "U1") (pin "108") (pinfunction "VDD_108") (pintype "passive"))
      (node (ref "U1") (pin "121") (pinfunction "VDD_121") (pintype "passive"))
      (node (ref "U1") (pin "131") (pinfunction "VDD_131") (pintype "passive"))
      (node (ref "U1") (pin "144") (pinfunction "VDD_144") (pintype "passive"))
      (node (ref "U1") (pin "17") (pinfunction "VDD_17") (pintype "passive"))
      (node (ref "U1") (pin "30") (pinfunction "VDD_30") (pintype "passive"))
      (node (ref "U1") (pin "32") (pinfunction "Vref+_32") (pintype "passive"))
      (node (ref "U1") (pin "39") (pinfunction "VDD_39") (pintype "passive"))
      (node (ref "U1") (pin "52") (pinfunction "VDD_52") (pintype "passive"))
      (node (ref "U1") (pin "62") (pinfunction "VDD_62") (pintype "passive"))
      (node (ref "U1") (pin "72") (pinfunction "VDD_72") (pintype "passive"))
      (node (ref "U1") (pin "84") (pinfunction "VDD_84") (pintype "passive"))
      (node (ref "U1") (pin "95") (pinfunction "VDD_95") (pintype "passive"))
      (node (ref "U5") (pin "2") (pinfunction "Vout_2") (pintype "passive"))
    )
    (net (code "67") (name "VDDA") (class "Default")
      (node (ref "C8") (pin "2") (pinfunction "2_2") (pintype "passive"))
      (node (ref "R12") (pin "1") (pinfunction "1_1") (pintype "passive"))
      (node (ref "U1") (pin "33") (pinfunction "VDDA_33") (pintype "passive"))
    )
    (net (code "68") (name "VUSB") (class "Default")
      (node (ref "2.4'/2.8'LCD") (pin "28") (pinfunction "BL_VDD_28") (pintype "passive"))
      (node (ref "C20") (pin "2") (pinfunction "2_2") (pintype "passive"))
      (node (ref "CC1") (pin "2") (pinfunction "1_2") (pintype "passive"))
      (node (ref "D6") (pin "2") (pintype "passive"))
      (node (ref "J1") (pin "1") (pinfunction "1_1") (pintype "passive"))
      (node (ref "J1") (pin "2") (pinfunction "2_2") (pintype "passive"))
      (node (ref "J1") (pin "3") (pinfunction "3_3") (pintype "passive"))
      (node (ref "J1") (pin "4") (pinfunction "4_4") (pintype "passive"))
      (node (ref "U2") (pin "29") (pinfunction "VUSB_29") (pintype "passive"))
      (node (ref "U5") (pin "3") (pinfunction "Vin_3") (pintype "passive"))
    )
    (net (code "69") (name "unconnected-(2.4'/2.8'LCD-MO-Pad32)") (class "Default")
      (node (ref "2.4'/2.8'LCD") (pin "32") (pinfunction "MO_32") (pintype "passive"))
    )
    (net (code "70") (name "unconnected-(RFID-IRQ-Pad5)") (class "Default")
      (node (ref "RFID") (pin "5") (pinfunction "IRQ_5") (pintype "passive"))
    )
    (net (code "71") (name "unconnected-(SD_CARD-CK-IN-Pad9)") (class "Default")
      (node (ref "SD_CARD") (pin "9") (pinfunction "CK-IN_9") (pintype "passive"))
    )
    (net (code "72") (name "unconnected-(SD_CARD-CK-OUT-Pad10)") (class "Default")
      (node (ref "SD_CARD") (pin "10") (pinfunction "CK-OUT_10") (pintype "passive"))
    )
    (net (code "73") (name "unconnected-(U1-PA0-WKUP{slash}U2_CTS{slash}U4_TX{slash}ETH_MII_CRS{slash}TIM2_CH1_ETR{slash}TIM5_CH1{slash}TIM8_ETR{slash}ADC123_IN0-Pad34)") (class "Default")
      (node (ref "U1") (pin "34") (pinfunction "PA0-WKUP/U2_CTS/U4_TX/ETH_MII_CRS/TIM2_CH1_ETR/TIM5_CH1/TIM8_ETR/ADC123_IN0_34") (pintype "passive"))
    )
    (net (code "74") (name "unconnected-(U1-PA1{slash}U2_RTS{slash}U4_RX{slash}ETH_RMII_REF_CLK{slash}ETH_MII_RX_CLK{slash}TIM2_CH2{slash}TIM5_CH2{slash}ADC123_IN1-Pad35)") (class "Default")
      (node (ref "U1") (pin "35") (pinfunction "PA1/U2_RTS/U4_RX/ETH_RMII_REF_CLK/ETH_MII_RX_CLK/TIM2_CH2/TIM5_CH2/ADC123_IN1_35") (pintype "passive"))
    )
    (net (code "75") (name "unconnected-(U1-PA2{slash}U2_TX{slash}TIM2_CH3{slash}TIM5_CH3{slash}TIM9_CH1{slash}ETH_MDIO{slash}ADC123_IN2-Pad36)") (class "Default")
      (node (ref "U1") (pin "36") (pinfunction "PA2/U2_TX/TIM2_CH3/TIM5_CH3/TIM9_CH1/ETH_MDIO/ADC123_IN2_36") (pintype "passive"))
    )
    (net (code "76") (name "unconnected-(U1-PA8{slash}TIM1_CH1{slash}U1_CK{slash}I2C3_SCL{slash}MCO1{slash}OTG_FS_SOF-Pad100)") (class "Default")
      (node (ref "U1") (pin "100") (pinfunction "PA8/TIM1_CH1/U1_CK/I2C3_SCL/MCO1/OTG_FS_SOF_100") (pintype "passive"))
    )
    (net (code "77") (name "unconnected-(U1-PA11{slash}TIM1_CH4{slash}U1_CTS{slash}CAN1_RX{slash}OTG_FS_DM-Pad103)") (class "Default")
      (node (ref "U1") (pin "103") (pinfunction "PA11/TIM1_CH4/U1_CTS/CAN1_RX/OTG_FS_DM_103") (pintype "passive"))
    )
    (net (code "78") (name "unconnected-(U1-PA12{slash}TIM1_ETR{slash}U1_RTS{slash}CAN1_TX{slash}OTG_FS_DP-Pad104)") (class "Default")
      (node (ref "U1") (pin "104") (pinfunction "PA12/TIM1_ETR/U1_RTS/CAN1_TX/OTG_FS_DP_104") (pintype "passive"))
    )
    (net (code "79") (name "unconnected-(U1-PA15{slash}JTDI{slash}SPI1_NSS{slash}SPI3_NSS{slash}TIM2_CH1_ETR{slash}I2S3_WS-Pad110)") (class "Default")
      (node (ref "U1") (pin "110") (pinfunction "PA15/JTDI/SPI1_NSS/SPI3_NSS/TIM2_CH1_ETR/I2S3_WS_110") (pintype "passive"))
    )
    (net (code "80") (name "unconnected-(U1-PB3{slash}JTDO{slash}TRACESWO{slash}TIM2_CH2{slash}SPI1_SCK{slash}SPI3_SCK{slash}I2S3_CK-Pad133)") (class "Default")
      (node (ref "U1") (pin "133") (pinfunction "PB3/JTDO/TRACESWO/TIM2_CH2/SPI1_SCK/SPI3_SCK/I2S3_CK_133") (pintype "passive"))
    )
    (net (code "81") (name "unconnected-(U1-PB4{slash}JNTRST{slash}TIM3_CH1{slash}SPI1_MISO{slash}SPI3_MISO{slash}I2S3ext_SD-Pad134)") (class "Default")
      (node (ref "U1") (pin "134") (pinfunction "PB4/JNTRST/TIM3_CH1/SPI1_MISO/SPI3_MISO/I2S3ext_SD_134") (pintype "passive"))
    )
    (net (code "82") (name "unconnected-(U1-PB5{slash}TIM3_CH2{slash}SPI1_MOSI{slash}SPI3_MOSI{slash}CAN2_RX{slash}I2C1_SMBA{slash}OTG_HS_ULPI_D7{slash}ETH_PPS_OUT{slash}DCMI_D10{slash}I2S3_SD-Pad135)") (class "Default")
      (node (ref "U1") (pin "135") (pinfunction "PB5/TIM3_CH2/SPI1_MOSI/SPI3_MOSI/CAN2_RX/I2C1_SMBA/OTG_HS_ULPI_D7/ETH_PPS_OUT/DCMI_D10/I2S3_SD_135") (pintype "passive"))
    )
    (net (code "83") (name "unconnected-(U1-PB6{slash}TIM4_CH1{slash}U1_TX{slash}CAN2_TX{slash}I2C1_SCL{slash}DCMI_D5-Pad136)") (class "Default")
      (node (ref "U1") (pin "136") (pinfunction "PB6/TIM4_CH1/U1_TX/CAN2_TX/I2C1_SCL/DCMI_D5_136") (pintype "passive"))
    )
    (net (code "84") (name "unconnected-(U1-PB7{slash}TIM4_CH2{slash}U1_RX{slash}FSMC_NL{slash}I2C1_SDA{slash}DCMI_VSYNC-Pad137)") (class "Default")
      (node (ref "U1") (pin "137") (pinfunction "PB7/TIM4_CH2/U1_RX/FSMC_NL/I2C1_SDA/DCMI_VSYNC_137") (pintype "passive"))
    )
    (net (code "85") (name "unconnected-(U1-PB8{slash}TIM4_CH3{slash}TIM10_CH1{slash}CAN1_RX{slash}SDIO_D4{slash}ETH_MII_TXD3{slash}I2C1_SCL{slash}DCMI_D6-Pad139)") (class "Default")
      (node (ref "U1") (pin "139") (pinfunction "PB8/TIM4_CH3/TIM10_CH1/CAN1_RX/SDIO_D4/ETH_MII_TXD3/I2C1_SCL/DCMI_D6_139") (pintype "passive"))
    )
    (net (code "86") (name "unconnected-(U1-PB9{slash}TIM4_CH4{slash}TIM11_CH1{slash}CAN1_TX{slash}SDIO_D5{slash}SPI2_NSS{slash}I2C1_SDA{slash}DCMI_D7{slash}I2S2_WS-Pad140)") (class "Default")
      (node (ref "U1") (pin "140") (pinfunction "PB9/TIM4_CH4/TIM11_CH1/CAN1_TX/SDIO_D5/SPI2_NSS/I2C1_SDA/DCMI_D7/I2S2_WS_140") (pintype "passive"))
    )
    (net (code "87") (name "unconnected-(U1-PB14{slash}SPI2_MISO{slash}TIM1_CH2N{slash}TIM8_CH2N{slash}TIM12_CH1{slash}U3_RTS{slash}OTG_HS_DM{slash}I2S2ext_SD-Pad75)") (class "Default")
      (node (ref "U1") (pin "75") (pinfunction "PB14/SPI2_MISO/TIM1_CH2N/TIM8_CH2N/TIM12_CH1/U3_RTS/OTG_HS_DM/I2S2ext_SD_75") (pintype "passive"))
    )
    (net (code "88") (name "unconnected-(U1-PC0{slash}OTG_HS_ULPI_STP{slash}ADC123_IN10-Pad26)") (class "Default")
      (node (ref "U1") (pin "26") (pinfunction "PC0/OTG_HS_ULPI_STP/ADC123_IN10_26") (pintype "passive"))
    )
    (net (code "89") (name "unconnected-(U1-PC1{slash}ETH_MDC{slash}ADC123_IN11-Pad27)") (class "Default")
      (node (ref "U1") (pin "27") (pinfunction "PC1/ETH_MDC/ADC123_IN11_27") (pintype "passive"))
    )
    (net (code "90") (name "unconnected-(U1-PC2{slash}SPI2_MISO{slash}OTG_HS_ULPI_DIR{slash}ETH_MII_TXD2{slash}I2S2ext_SD{slash}ADC123_IN12-Pad28)") (class "Default")
      (node (ref "U1") (pin "28") (pinfunction "PC2/SPI2_MISO/OTG_HS_ULPI_DIR/ETH_MII_TXD2/I2S2ext_SD/ADC123_IN12_28") (pintype "passive"))
    )
    (net (code "91") (name "unconnected-(U1-PC3{slash}SPI2_MOSI{slash}OTG_HS_ULPI_NXT{slash}ETH_MII_TX_CLK{slash}I2S2_SD{slash}ADC123_IN13-Pad29)") (class "Default")
      (node (ref "U1") (pin "29") (pinfunction "PC3/SPI2_MOSI/OTG_HS_ULPI_NXT/ETH_MII_TX_CLK/I2S2_SD/ADC123_IN13_29") (pintype "passive"))
    )
    (net (code "92") (name "unconnected-(U1-PC5{slash}ETH_MII_RXD1{slash}ETH_RMII_RXD1{slash}ADC12_IN15-Pad45)") (class "Default")
      (node (ref "U1") (pin "45") (pinfunction "PC5/ETH_MII_RXD1/ETH_RMII_RXD1/ADC12_IN15_45") (pintype "passive"))
    )
    (net (code "93") (name "unconnected-(U1-PC6{slash}TIM3_CH1{slash}TIM8_CH1{slash}U6_TX{slash}SDIO_D6{slash}DCMI_D0{slash}I2S2_MCK-Pad96)") (class "Default")
      (node (ref "U1") (pin "96") (pinfunction "PC6/TIM3_CH1/TIM8_CH1/U6_TX/SDIO_D6/DCMI_D0/I2S2_MCK_96") (pintype "passive"))
    )
    (net (code "94") (name "unconnected-(U1-PC7{slash}TIM3_CH2{slash}TIM8_CH2{slash}U6_RX{slash}SDIO_D7{slash}DCMI_D1{slash}I2S3_MCK-Pad97)") (class "Default")
      (node (ref "U1") (pin "97") (pinfunction "PC7/TIM3_CH2/TIM8_CH2/U6_RX/SDIO_D7/DCMI_D1/I2S3_MCK_97") (pintype "passive"))
    )
    (net (code "95") (name "unconnected-(U1-PD3{slash}FSMC_CLK{slash}U2_CTS-Pad117)") (class "Default")
      (node (ref "U1") (pin "117") (pinfunction "PD3/FSMC_CLK/U2_CTS_117") (pintype "passive"))
    )
    (net (code "96") (name "unconnected-(U1-PD6{slash}FSMC_NWAIT{slash}U2_RX-Pad122)") (class "Default")
      (node (ref "U1") (pin "122") (pinfunction "PD6/FSMC_NWAIT/U2_RX_122") (pintype "passive"))
    )
    (net (code "97") (name "unconnected-(U1-PD7{slash}FSMC_NE1{slash}FSMC_NCE2{slash}U2_CK-Pad123)") (class "Default")
      (node (ref "U1") (pin "123") (pinfunction "PD7/FSMC_NE1/FSMC_NCE2/U2_CK_123") (pintype "passive"))
    )
    (net (code "98") (name "unconnected-(U1-PD11{slash}FSMC_A16{slash}FSMC_CLE{slash}U3_CTS-Pad80)") (class "Default")
      (node (ref "U1") (pin "80") (pinfunction "PD11/FSMC_A16/FSMC_CLE/U3_CTS_80") (pintype "passive"))
    )
    (net (code "99") (name "unconnected-(U1-PD12{slash}FSMC_A17{slash}FSMC_ALE{slash}TIM4_CH1{slash}U3_RTS-Pad81)") (class "Default")
      (node (ref "U1") (pin "81") (pinfunction "PD12/FSMC_A17/FSMC_ALE/TIM4_CH1/U3_RTS_81") (pintype "passive"))
    )
    (net (code "100") (name "unconnected-(U1-PD13{slash}FSMC_A18{slash}TIM4_CH2-Pad82)") (class "Default")
      (node (ref "U1") (pin "82") (pinfunction "PD13/FSMC_A18/TIM4_CH2_82") (pintype "passive"))
    )
    (net (code "101") (name "unconnected-(U1-PDR_ON-Pad143)") (class "Default")
      (node (ref "U1") (pin "143") (pinfunction "PDR_ON_143") (pintype "passive"))
    )
    (net (code "102") (name "unconnected-(U1-PE0{slash}TIM4_ETR{slash}FSMC_NBL0{slash}DCMI_D2-Pad141)") (class "Default")
      (node (ref "U1") (pin "141") (pinfunction "PE0/TIM4_ETR/FSMC_NBL0/DCMI_D2_141") (pintype "passive"))
    )
    (net (code "103") (name "unconnected-(U1-PE1{slash}FSMC_NBL1{slash}DCMI_D3-Pad142)") (class "Default")
      (node (ref "U1") (pin "142") (pinfunction "PE1/FSMC_NBL1/DCMI_D3_142") (pintype "passive"))
    )
    (net (code "104") (name "unconnected-(U1-PE2{slash}TRACECLK{slash}FSMC_A23{slash}ETH_MII_TXD3-Pad1)") (class "Default")
      (node (ref "U1") (pin "1") (pinfunction "PE2/TRACECLK/FSMC_A23/ETH_MII_TXD3_1") (pintype "passive"))
    )
    (net (code "105") (name "unconnected-(U1-PE3{slash}TRACED0{slash}FSMC_A19-Pad2)") (class "Default")
      (node (ref "U1") (pin "2") (pinfunction "PE3/TRACED0/FSMC_A19_2") (pintype "passive"))
    )
    (net (code "106") (name "unconnected-(U1-PE4{slash}TRACED1{slash}FSMC_A20{slash}DCMI_D4-Pad3)") (class "Default")
      (node (ref "U1") (pin "3") (pinfunction "PE4/TRACED1/FSMC_A20/DCMI_D4_3") (pintype "passive"))
    )
    (net (code "107") (name "unconnected-(U1-PE5{slash}TRACED2{slash}FSMC_A21{slash}TIM9_CH1{slash}DCMI_D6-Pad4)") (class "Default")
      (node (ref "U1") (pin "4") (pinfunction "PE5/TRACED2/FSMC_A21/TIM9_CH1/DCMI_D6_4") (pintype "passive"))
    )
    (net (code "108") (name "unconnected-(U1-PE6{slash}TRACED3{slash}FSMC_A22{slash}TIM9_CH2{slash}DCMI_D7-Pad5)") (class "Default")
      (node (ref "U1") (pin "5") (pinfunction "PE6/TRACED3/FSMC_A22/TIM9_CH2/DCMI_D7_5") (pintype "passive"))
    )
    (net (code "109") (name "unconnected-(U1-PF0{slash}FSMC_A0{slash}I2C2_SDA-Pad10)") (class "Default")
      (node (ref "U1") (pin "10") (pinfunction "PF0/FSMC_A0/I2C2_SDA_10") (pintype "passive"))
    )
    (net (code "110") (name "unconnected-(U1-PF1{slash}FSMC_A1{slash}I2C2_SCL-Pad11)") (class "Default")
      (node (ref "U1") (pin "11") (pinfunction "PF1/FSMC_A1/I2C2_SCL_11") (pintype "passive"))
    )
    (net (code "111") (name "unconnected-(U1-PF2{slash}FSMC_A2{slash}I2C2_SMBA-Pad12)") (class "Default")
      (node (ref "U1") (pin "12") (pinfunction "PF2/FSMC_A2/I2C2_SMBA_12") (pintype "passive"))
    )
    (net (code "112") (name "unconnected-(U1-PF3{slash}FSMC_A3{slash}ADC3_IN9-Pad13)") (class "Default")
      (node (ref "U1") (pin "13") (pinfunction "PF3/FSMC_A3/ADC3_IN9_13") (pintype "passive"))
    )
    (net (code "113") (name "unconnected-(U1-PF4{slash}FSMC_A4{slash}ADC3_IN14-Pad14)") (class "Default")
      (node (ref "U1") (pin "14") (pinfunction "PF4/FSMC_A4/ADC3_IN14_14") (pintype "passive"))
    )
    (net (code "114") (name "unconnected-(U1-PF5{slash}FSMC_A5{slash}ADC3_IN15-Pad15)") (class "Default")
      (node (ref "U1") (pin "15") (pinfunction "PF5/FSMC_A5/ADC3_IN15_15") (pintype "passive"))
    )
    (net (code "115") (name "unconnected-(U1-PF6{slash}TIM10_CH1{slash}FSMC_NIORD{slash}ADC3_IN4-Pad18)") (class "Default")
      (node (ref "U1") (pin "18") (pinfunction "PF6/TIM10_CH1/FSMC_NIORD/ADC3_IN4_18") (pintype "passive"))
    )
    (net (code "116") (name "unconnected-(U1-PF7{slash}TIM11_CH1{slash}FSMC_NREG{slash}ADC3_IN5-Pad19)") (class "Default")
      (node (ref "U1") (pin "19") (pinfunction "PF7/TIM11_CH1/FSMC_NREG/ADC3_IN5_19") (pintype "passive"))
    )
    (net (code "117") (name "unconnected-(U1-PF8{slash}TIM13_CH1{slash}FSMC_NIOWR{slash}ADC3_IN6-Pad20)") (class "Default")
      (node (ref "U1") (pin "20") (pinfunction "PF8/TIM13_CH1/FSMC_NIOWR/ADC3_IN6_20") (pintype "passive"))
    )
    (net (code "118") (name "unconnected-(U1-PF9{slash}TIM14_CH1{slash}FSMC_CD{slash}ADC3_IN7-Pad21)") (class "Default")
      (node (ref "U1") (pin "21") (pinfunction "PF9/TIM14_CH1/FSMC_CD/ADC3_IN7_21") (pintype "passive"))
    )
    (net (code "119") (name "unconnected-(U1-PF10{slash}FSMC_INTR{slash}ADC3_IN8-Pad22)") (class "Default")
      (node (ref "U1") (pin "22") (pinfunction "PF10/FSMC_INTR/ADC3_IN8_22") (pintype "passive"))
    )
    (net (code "120") (name "unconnected-(U1-PF13{slash}FSMC_A7-Pad53)") (class "Default")
      (node (ref "U1") (pin "53") (pinfunction "PF13/FSMC_A7_53") (pintype "passive"))
    )
    (net (code "121") (name "unconnected-(U1-PF14{slash}FSMC_A8-Pad54)") (class "Default")
      (node (ref "U1") (pin "54") (pinfunction "PF14/FSMC_A8_54") (pintype "passive"))
    )
    (net (code "122") (name "unconnected-(U1-PF15{slash}FSMC_A9-Pad55)") (class "Default")
      (node (ref "U1") (pin "55") (pinfunction "PF15/FSMC_A9_55") (pintype "passive"))
    )
    (net (code "123") (name "unconnected-(U1-PG0{slash}FSMC_A10-Pad56)") (class "Default")
      (node (ref "U1") (pin "56") (pinfunction "PG0/FSMC_A10_56") (pintype "passive"))
    )
    (net (code "124") (name "unconnected-(U1-PG1{slash}FSMC_A11-Pad57)") (class "Default")
      (node (ref "U1") (pin "57") (pinfunction "PG1/FSMC_A11_57") (pintype "passive"))
    )
    (net (code "125") (name "unconnected-(U1-PG5{slash}FSMC_A15-Pad90)") (class "Default")
      (node (ref "U1") (pin "90") (pinfunction "PG5/FSMC_A15_90") (pintype "passive"))
    )
    (net (code "126") (name "unconnected-(U1-PG6{slash}FSMC_INT2-Pad91)") (class "Default")
      (node (ref "U1") (pin "91") (pinfunction "PG6/FSMC_INT2_91") (pintype "passive"))
    )
    (net (code "127") (name "unconnected-(U1-PG7{slash}FSMC_INT3{slash}U6_CK-Pad92)") (class "Default")
      (node (ref "U1") (pin "92") (pinfunction "PG7/FSMC_INT3/U6_CK_92") (pintype "passive"))
    )
    (net (code "128") (name "unconnected-(U1-PG8{slash}U6_RTS{slash}ETH_PPS_OUT-Pad93)") (class "Default")
      (node (ref "U1") (pin "93") (pinfunction "PG8/U6_RTS/ETH_PPS_OUT_93") (pintype "passive"))
    )
    (net (code "129") (name "unconnected-(U1-PG9{slash}FSMC_NE2{slash}FSMC_NCE3{slash}U6_RX-Pad124)") (class "Default")
      (node (ref "U1") (pin "124") (pinfunction "PG9/FSMC_NE2/FSMC_NCE3/U6_RX_124") (pintype "passive"))
    )
    (net (code "130") (name "unconnected-(U1-PG10{slash}FSMC_NCE4_1{slash}FSMC_NE3-Pad125)") (class "Default")
      (node (ref "U1") (pin "125") (pinfunction "PG10/FSMC_NCE4_1/FSMC_NE3_125") (pintype "passive"))
    )
    (net (code "131") (name "unconnected-(U1-PG11{slash}FSMC_NCE4_2{slash}ETH_MII_TX_EN{slash}ETH_RMII_TX_EN-Pad126)") (class "Default")
      (node (ref "U1") (pin "126") (pinfunction "PG11/FSMC_NCE4_2/ETH_MII_TX_EN/ETH_RMII_TX_EN_126") (pintype "passive"))
    )
    (net (code "132") (name "unconnected-(U1-PG13{slash}FSMC_A24{slash}U6_CTS{slash}ETH_MII_TXD0{slash}ETH_RMII_TXD0-Pad128)") (class "Default")
      (node (ref "U1") (pin "128") (pinfunction "PG13/FSMC_A24/U6_CTS/ETH_MII_TXD0/ETH_RMII_TXD0_128") (pintype "passive"))
    )
    (net (code "133") (name "unconnected-(U1-PG14{slash}FSMC_A25{slash}U6_TX{slash}ETH_MII_TXD1{slash}ETH_RMII_TXD1-Pad129)") (class "Default")
      (node (ref "U1") (pin "129") (pinfunction "PG14/FSMC_A25/U6_TX/ETH_MII_TXD1/ETH_RMII_TXD1_129") (pintype "passive"))
    )
    (net (code "134") (name "unconnected-(U1-PG15{slash}U6_CTS{slash}DCMI_D13-Pad132)") (class "Default")
      (node (ref "U1") (pin "132") (pinfunction "PG15/U6_CTS/DCMI_D13_132") (pintype "passive"))
    )
    (net (code "135") (name "unconnected-(U2-ADC0-Pad13)") (class "Default")
      (node (ref "U2") (pin "13") (pinfunction "ADC0_13") (pintype "passive"))
    )
    (net (code "136") (name "unconnected-(U2-ADC1-Pad12)") (class "Default")
      (node (ref "U2") (pin "12") (pinfunction "ADC1_12") (pintype "passive"))
    )
    (net (code "137") (name "unconnected-(U2-GPS_RX-Pad21)") (class "Default")
      (node (ref "U2") (pin "21") (pinfunction "GPS_RX_21") (pintype "passive"))
    )
    (net (code "138") (name "unconnected-(U2-HST_RX-Pad26)") (class "Default")
      (node (ref "U2") (pin "26") (pinfunction "HST_RX_26") (pintype "passive"))
    )
    (net (code "139") (name "unconnected-(U2-HST_TX-Pad25)") (class "Default")
      (node (ref "U2") (pin "25") (pinfunction "HST_TX_25") (pintype "passive"))
    )
    (net (code "140") (name "unconnected-(U2-I2C2_SCL-Pad10)") (class "Default")
      (node (ref "U2") (pin "10") (pinfunction "I2C2_SCL_10") (pintype "passive"))
    )
    (net (code "141") (name "unconnected-(U2-I2C2_SDA-Pad11)") (class "Default")
      (node (ref "U2") (pin "11") (pinfunction "I2C2_SDA_11") (pintype "passive"))
    )
    (net (code "142") (name "unconnected-(U2-IO2-Pad19)") (class "Default")
      (node (ref "U2") (pin "19") (pinfunction "IO2_19") (pintype "passive"))
    )
    (net (code "143") (name "unconnected-(U2-IO3-Pad20)") (class "Default")
      (node (ref "U2") (pin "20") (pinfunction "IO3_20") (pintype "passive"))
    )
    (net (code "144") (name "unconnected-(U2-IO6-Pad23)") (class "Default")
      (node (ref "U2") (pin "23") (pinfunction "IO6_23") (pintype "passive"))
    )
    (net (code "145") (name "unconnected-(U2-IO7-Pad24)") (class "Default")
      (node (ref "U2") (pin "24") (pinfunction "IO7_24") (pintype "passive"))
    )
    (net (code "146") (name "unconnected-(U2-IO25-Pad1)") (class "Default")
      (node (ref "U2") (pin "1") (pinfunction "IO25_1") (pintype "passive"))
    )
    (net (code "147") (name "unconnected-(U2-IO29-Pad4)") (class "Default")
      (node (ref "U2") (pin "4") (pinfunction "IO29_4") (pintype "passive"))
    )
    (net (code "148") (name "unconnected-(U2-IO30-Pad2)") (class "Default")
      (node (ref "U2") (pin "2") (pinfunction "IO30_2") (pintype "passive"))
    )
    (net (code "149") (name "unconnected-(U2-IO326-Pad3)") (class "Default")
      (node (ref "U2") (pin "3") (pinfunction "IO326_3") (pintype "passive"))
    )
    (net (code "150") (name "unconnected-(U2-LCD_CS-Pad9)") (class "Default")
      (node (ref "U2") (pin "9") (pinfunction "LCD_CS_9") (pintype "passive"))
    )
    (net (code "151") (name "unconnected-(U2-LCD_DC-Pad6)") (class "Default")
      (node (ref "U2") (pin "6") (pinfunction "LCD_DC_6") (pintype "passive"))
    )
    (net (code "152") (name "unconnected-(U2-LCD_DIO-Pad7)") (class "Default")
      (node (ref "U2") (pin "7") (pinfunction "LCD_DIO_7") (pintype "passive"))
    )
    (net (code "153") (name "unconnected-(U2-LCD_RST-Pad8)") (class "Default")
      (node (ref "U2") (pin "8") (pinfunction "LCD_RST_8") (pintype "passive"))
    )
    (net (code "154") (name "unconnected-(U2-LCD_SCK-Pad5)") (class "Default")
      (node (ref "U2") (pin "5") (pinfunction "LCD_SCK_5") (pintype "passive"))
    )
    (net (code "155") (name "unconnected-(U2-RESET-Pad28)") (class "Default")
      (node (ref "U2") (pin "28") (pinfunction "RESET_28") (pintype "passive"))
    )
    (net (code "156") (name "unconnected-(U2-VBAT-Pad15)") (class "Default")
      (node (ref "U2") (pin "15") (pinfunction "VBAT_15") (pintype "passive"))
    )
    (net (code "157") (name "unconnected-(U2-VIO-Pad14)") (class "Default")
      (node (ref "U2") (pin "14") (pinfunction "VIO_14") (pintype "passive"))
    )
    (net (code "158") (name "unconnected-(U4-D+-Pad3)") (class "Default")
      (node (ref "U4") (pin "3") (pinfunction "D+_3") (pintype "passive"))
    )
    (net (code "159") (name "unconnected-(U4-D--Pad2)") (class "Default")
      (node (ref "U4") (pin "2") (pinfunction "D-_2") (pintype "passive"))
    )
    (net (code "160") (name "unconnected-(U4-NC-Pad4)") (class "Default")
      (node (ref "U4") (pin "4") (pinfunction "NC_4") (pintype "passive"))
    )
  )
)
